# Input.net
KiCad netlist of a schematic drawn in Altium Designer
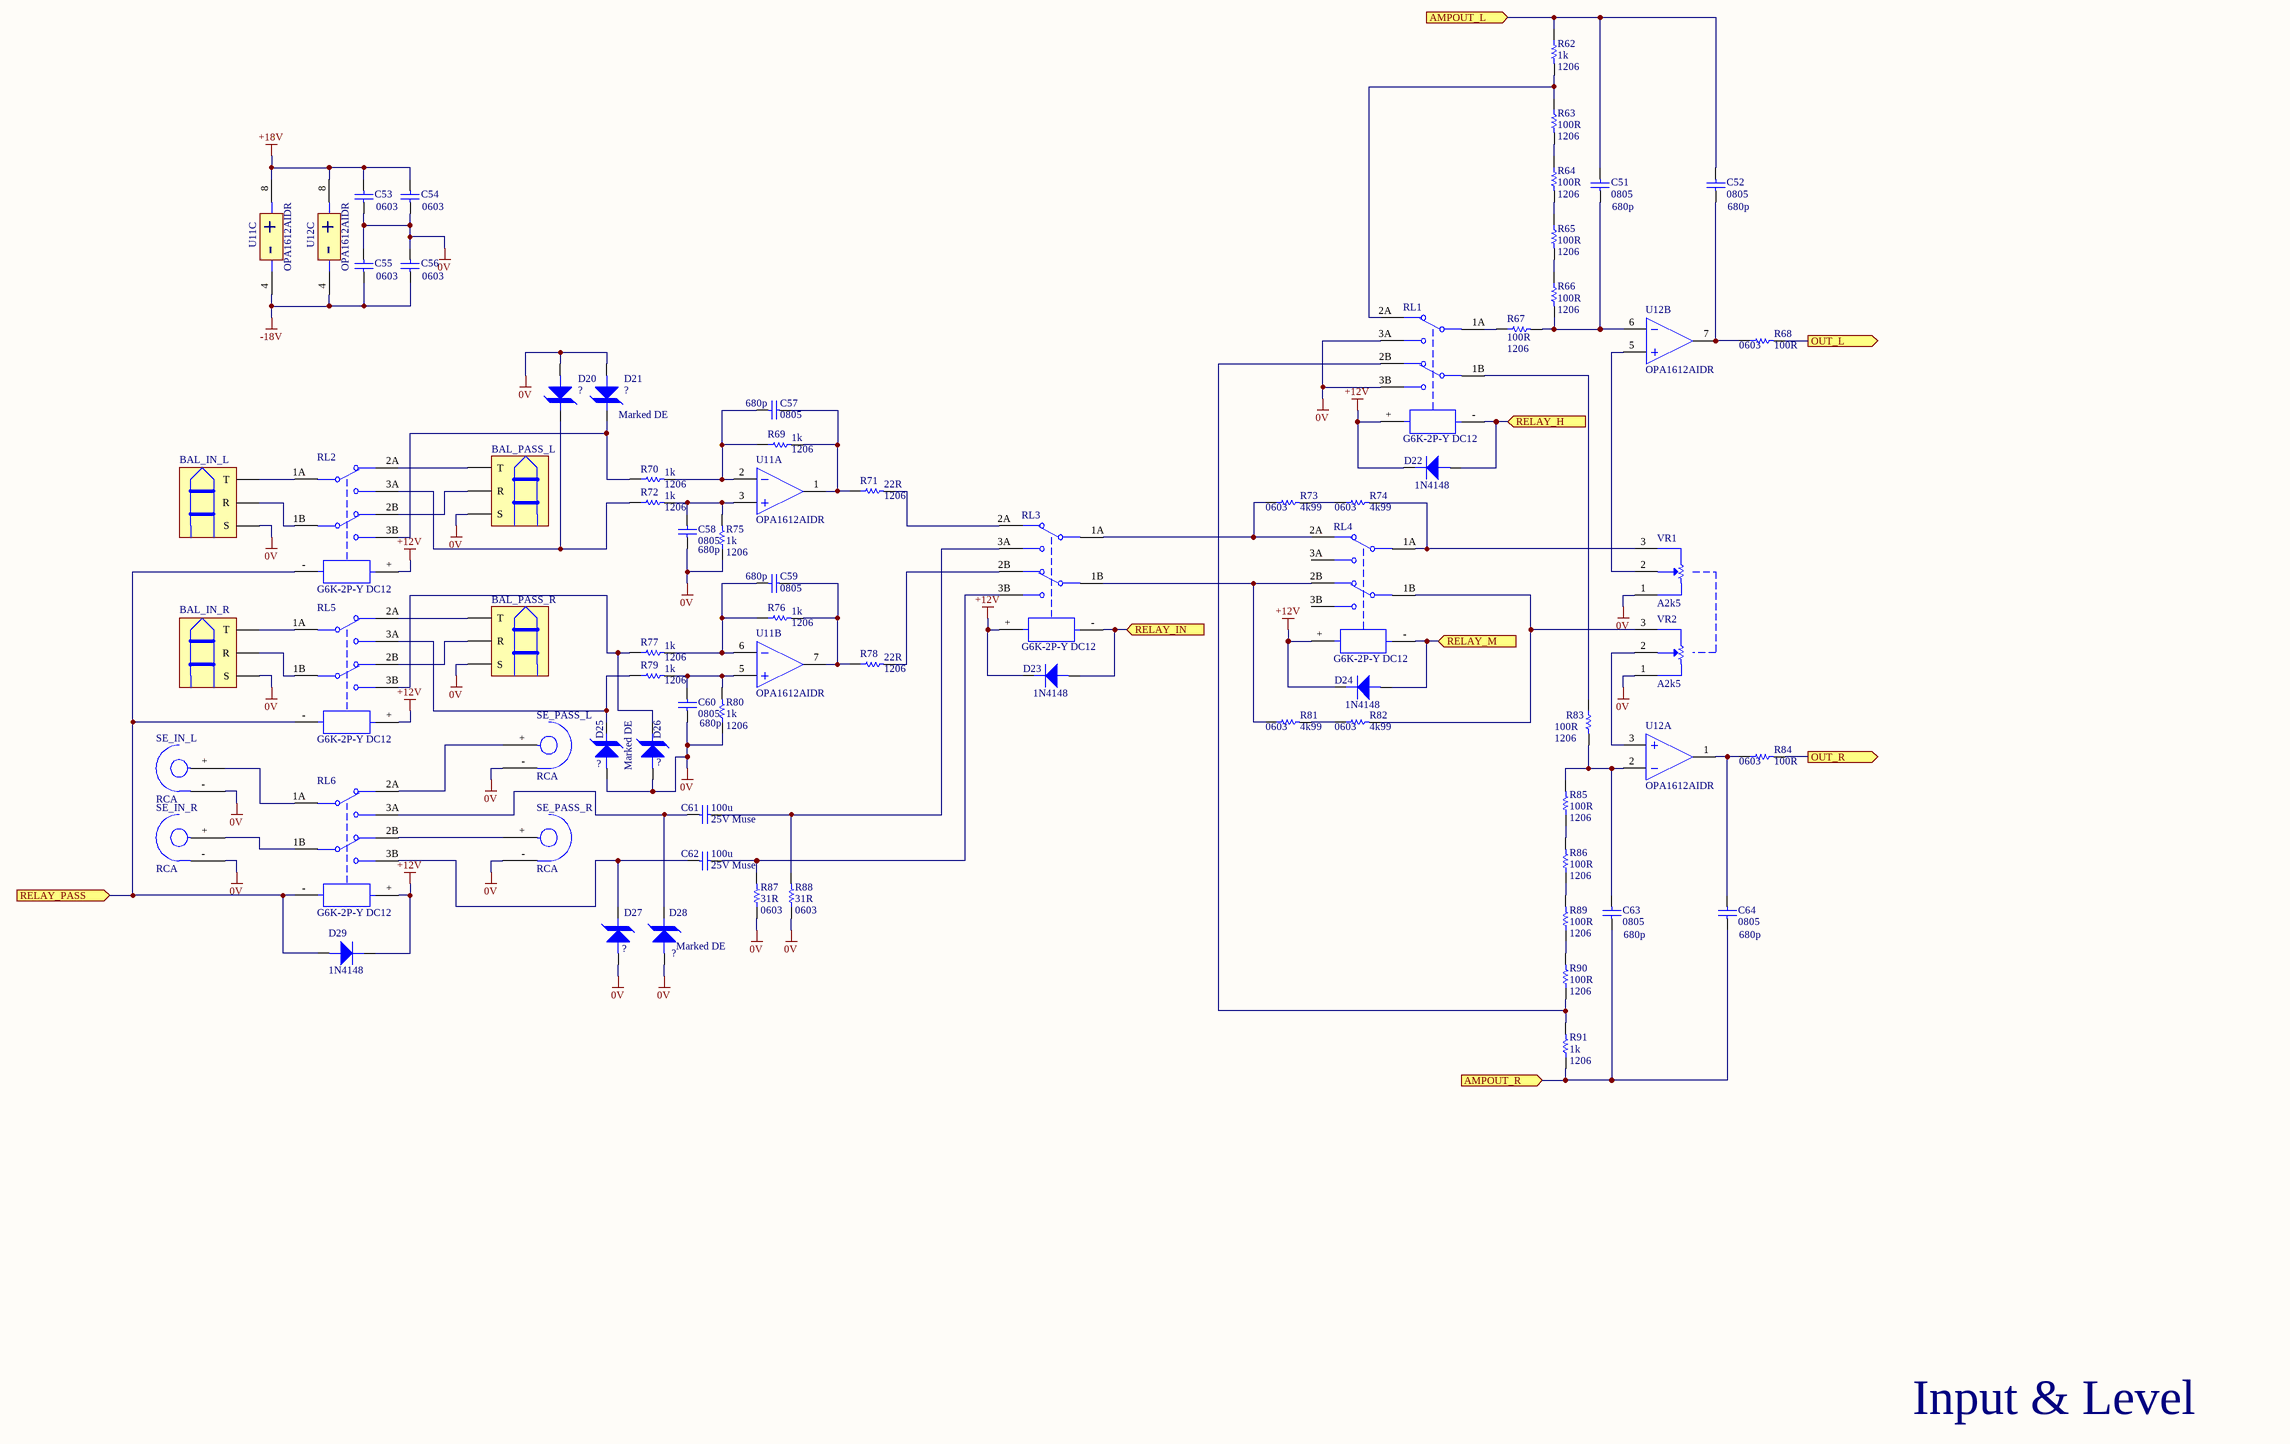
[diagram p0: Input.SchDoc]

(export (version "E")
  (design (tool "Eeschema 10.0.6"))
  (components
    (comp (ref "BAL_IN_L")
      (value "SJ-63053A")
      (footprint "SJ-63053A")
      (fields (field (name "MANUFACTURER") "Same Sky"))
      (libsource (lib "Topping_L50") (part "SJ-63053A"))
    )
    (comp (ref "BAL_IN_R")
      (value "SJ-63053A")
      (footprint "SJ-63053A")
      (fields (field (name "MANUFACTURER") "Same Sky"))
      (libsource (lib "Topping_L50") (part "SJ-63053A"))
    )
    (comp (ref "BAL_PASS_L")
      (value "SJ-63053A")
      (footprint "SJ-63053A")
      (fields (field (name "MANUFACTURER") "Same Sky"))
      (libsource (lib "") (part "SJ-63053A_1"))
    )
    (comp (ref "BAL_PASS_R")
      (value "SJ-63053A")
      (footprint "SJ-63053A")
      (fields (field (name "MANUFACTURER") "Same Sky"))
      (libsource (lib "") (part "SJ-63053A_1"))
    )
    (comp (ref "C51")
      (value "680p")
      (footprint "CAPC2012X14N")
      (description "Generic MLCC 0805 Non Polarized Capacitor")
      (fields
        (field (name "MANUFACTURER") "Generic")
        (field (name "PACKAGE") "0805")
        (field (name "Comment") "C_MLCC_0805")
      )
      (libsource (lib "Topping_L50") (part "C_MLCC_0805"))
    )
    (comp (ref "C52")
      (value "680p")
      (footprint "CAPC2012X14N")
      (description "Generic MLCC 0805 Non Polarized Capacitor")
      (fields
        (field (name "MANUFACTURER") "Generic")
        (field (name "PACKAGE") "0805")
        (field (name "Comment") "C_MLCC_0805")
      )
      (libsource (lib "Topping_L50") (part "C_MLCC_0805"))
    )
    (comp (ref "C53")
      (value "C_MLCC_0603")
      (footprint "CAPC1608X09N")
      (description "Generic MLCC 0603 Non Polarized Capacitor")
      (fields (field (name "MANUFACTURER") "Generic") (field (name "PACKAGE") "0603"))
      (libsource (lib "Topping_L50") (part "C_MLCC_0603"))
    )
    (comp (ref "C54")
      (value "C_MLCC_0603")
      (footprint "CAPC1608X09N")
      (description "Generic MLCC 0603 Non Polarized Capacitor")
      (fields (field (name "MANUFACTURER") "Generic") (field (name "PACKAGE") "0603"))
      (libsource (lib "Topping_L50") (part "C_MLCC_0603"))
    )
    (comp (ref "C55")
      (value "C_MLCC_0603")
      (footprint "CAPC1608X09N")
      (description "Generic MLCC 0603 Non Polarized Capacitor")
      (fields (field (name "MANUFACTURER") "Generic") (field (name "PACKAGE") "0603"))
      (libsource (lib "Topping_L50") (part "C_MLCC_0603"))
    )
    (comp (ref "C56")
      (value "C_MLCC_0603")
      (footprint "CAPC1608X09N")
      (description "Generic MLCC 0603 Non Polarized Capacitor")
      (fields (field (name "MANUFACTURER") "Generic") (field (name "PACKAGE") "0603"))
      (libsource (lib "Topping_L50") (part "C_MLCC_0603"))
    )
    (comp (ref "C57")
      (value "680p")
      (footprint "CAPC2012X14N")
      (description "Generic MLCC 0805 Non Polarized Capacitor")
      (fields
        (field (name "MANUFACTURER") "Generic")
        (field (name "PACKAGE") "0805")
        (field (name "Comment") "C_MLCC_0805")
      )
      (libsource (lib "Topping_L50") (part "C_MLCC_0805"))
    )
    (comp (ref "C58")
      (value "680p")
      (footprint "CAPC2012X14N")
      (description "Generic MLCC 0805 Non Polarized Capacitor")
      (fields
        (field (name "MANUFACTURER") "Generic")
        (field (name "PACKAGE") "0805")
        (field (name "Comment") "C_MLCC_0805")
      )
      (libsource (lib "Topping_L50") (part "C_MLCC_0805"))
    )
    (comp (ref "C59")
      (value "680p")
      (footprint "CAPC2012X14N")
      (description "Generic MLCC 0805 Non Polarized Capacitor")
      (fields
        (field (name "MANUFACTURER") "Generic")
        (field (name "PACKAGE") "0805")
        (field (name "Comment") "C_MLCC_0805")
      )
      (libsource (lib "Topping_L50") (part "C_MLCC_0805"))
    )
    (comp (ref "C60")
      (value "680p")
      (footprint "CAPC2012X14N")
      (description "Generic MLCC 0805 Non Polarized Capacitor")
      (fields
        (field (name "MANUFACTURER") "Generic")
        (field (name "PACKAGE") "0805")
        (field (name "Comment") "C_MLCC_0805")
      )
      (libsource (lib "Topping_L50") (part "C_MLCC_0805"))
    )
    (comp (ref "C61")
      (value "100u")
      (footprint "CAPC2012X14N")
      (description "Generic MLCC 0805 Non Polarized Capacitor")
      (fields
        (field (name "MANUFACTURER") "Generic")
        (field (name "NOTES") "25V Muse")
        (field (name "Comment") "C_MLCC_0805")
      )
      (libsource (lib "Topping_L50") (part "C_MLCC_0805"))
    )
    (comp (ref "C62")
      (value "100u")
      (footprint "CAPC2012X14N")
      (description "Generic MLCC 0805 Non Polarized Capacitor")
      (fields
        (field (name "MANUFACTURER") "Generic")
        (field (name "NOTES") "25V Muse")
        (field (name "Comment") "C_MLCC_0805")
      )
      (libsource (lib "Topping_L50") (part "C_MLCC_0805"))
    )
    (comp (ref "C63")
      (value "680p")
      (footprint "CAPC2012X14N")
      (description "Generic MLCC 0805 Non Polarized Capacitor")
      (fields
        (field (name "MANUFACTURER") "Generic")
        (field (name "PACKAGE") "0805")
        (field (name "Comment") "C_MLCC_0805")
      )
      (libsource (lib "Topping_L50") (part "C_MLCC_0805"))
    )
    (comp (ref "C64")
      (value "680p")
      (footprint "CAPC2012X14N")
      (description "Generic MLCC 0805 Non Polarized Capacitor")
      (fields
        (field (name "MANUFACTURER") "Generic")
        (field (name "PACKAGE") "0805")
        (field (name "Comment") "C_MLCC_0805")
      )
      (libsource (lib "Topping_L50") (part "C_MLCC_0805"))
    )
    (comp (ref "D20")
      (value "?")
      (footprint "DIOM4336X24N")
      (description "Generic TVS diode")
      (fields (field (name "MANUFACTURER") "Bourns") (field (name "MANUFACTURER PART NUMBER") "SMBJ30A"))
      (libsource (lib "Topping_L50") (part "TVS"))
    )
    (comp (ref "D21")
      (value "?")
      (footprint "DIOM4336X24N")
      (description "Generic TVS diode")
      (fields (field (name "MANUFACTURER") "Bourns") (field (name "MANUFACTURER PART NUMBER") "SMBJ30A"))
      (libsource (lib "Topping_L50") (part "TVS"))
    )
    (comp (ref "D22")
      (value "1N4148")
      (description "Generic small signal diode")
      (fields (field (name "MANUFACTURER") "Generic") (field (name "MANUFACTURER PART NUMBER") "BAT48ZFILM"))
      (libsource (lib "Topping_L50") (part "1N4148"))
    )
    (comp (ref "D23")
      (value "1N4148")
      (description "Generic small signal diode")
      (fields (field (name "MANUFACTURER") "Generic") (field (name "MANUFACTURER PART NUMBER") "BAT48ZFILM"))
      (libsource (lib "Topping_L50") (part "1N4148"))
    )
    (comp (ref "D24")
      (value "1N4148")
      (description "Generic small signal diode")
      (fields (field (name "MANUFACTURER") "Generic") (field (name "MANUFACTURER PART NUMBER") "BAT48ZFILM"))
      (libsource (lib "Topping_L50") (part "1N4148"))
    )
    (comp (ref "D25")
      (value "?")
      (footprint "DIOM4336X24N")
      (description "Generic TVS diode")
      (fields (field (name "MANUFACTURER") "Bourns") (field (name "MANUFACTURER PART NUMBER") "SMBJ30A"))
      (libsource (lib "Topping_L50") (part "TVS"))
    )
    (comp (ref "D26")
      (value "?")
      (footprint "DIOM4336X24N")
      (description "Generic TVS diode")
      (fields (field (name "MANUFACTURER") "Bourns") (field (name "MANUFACTURER PART NUMBER") "SMBJ30A"))
      (libsource (lib "Topping_L50") (part "TVS"))
    )
    (comp (ref "D27")
      (value "?")
      (footprint "DIOM4336X24N")
      (description "Generic TVS diode")
      (fields (field (name "MANUFACTURER") "Bourns") (field (name "MANUFACTURER PART NUMBER") "SMBJ30A"))
      (libsource (lib "Topping_L50") (part "TVS"))
    )
    (comp (ref "D28")
      (value "?")
      (footprint "DIOM4336X24N")
      (description "Generic TVS diode")
      (fields (field (name "MANUFACTURER") "Bourns") (field (name "MANUFACTURER PART NUMBER") "SMBJ30A"))
      (libsource (lib "Topping_L50") (part "TVS"))
    )
    (comp (ref "D29")
      (value "1N4148")
      (description "Generic small signal diode")
      (fields (field (name "MANUFACTURER") "Generic") (field (name "MANUFACTURER PART NUMBER") "BAT48ZFILM"))
      (libsource (lib "Topping_L50") (part "1N4148"))
    )
    (comp (ref "R62")
      (value "1k")
      (footprint "RESC3116X06N")
      (description "Generic 1206 Single Resistor")
      (fields
        (field (name "MANUFACTURER") "Generic")
        (field (name "PACKAGE") "1206")
        (field (name "Comment") "R")
      )
      (libsource (lib "Topping_L50") (part "R_1206"))
    )
    (comp (ref "R63")
      (value "100R")
      (footprint "RESC3116X06N")
      (description "Generic 1206 Single Resistor")
      (fields
        (field (name "MANUFACTURER") "Generic")
        (field (name "PACKAGE") "1206")
        (field (name "Comment") "R")
      )
      (libsource (lib "Topping_L50") (part "R_1206"))
    )
    (comp (ref "R64")
      (value "100R")
      (footprint "RESC3116X06N")
      (description "Generic 1206 Single Resistor")
      (fields
        (field (name "MANUFACTURER") "Generic")
        (field (name "PACKAGE") "1206")
        (field (name "Comment") "R")
      )
      (libsource (lib "Topping_L50") (part "R_1206"))
    )
    (comp (ref "R65")
      (value "100R")
      (footprint "RESC3116X06N")
      (description "Generic 1206 Single Resistor")
      (fields
        (field (name "MANUFACTURER") "Generic")
        (field (name "PACKAGE") "1206")
        (field (name "Comment") "R")
      )
      (libsource (lib "Topping_L50") (part "R_1206"))
    )
    (comp (ref "R66")
      (value "100R")
      (footprint "RESC3116X06N")
      (description "Generic 1206 Single Resistor")
      (fields
        (field (name "MANUFACTURER") "Generic")
        (field (name "PACKAGE") "1206")
        (field (name "Comment") "R")
      )
      (libsource (lib "Topping_L50") (part "R_1206"))
    )
    (comp (ref "R67")
      (value "100R")
      (footprint "RESC3116X06N")
      (description "Generic 1206 Single Resistor")
      (fields
        (field (name "MANUFACTURER") "Generic")
        (field (name "PACKAGE") "1206")
        (field (name "Comment") "R")
      )
      (libsource (lib "Topping_L50") (part "R_1206"))
    )
    (comp (ref "R68")
      (value "100R")
      (footprint "RESC1608X06N")
      (description "Generic 0603 Single Resistor")
      (fields
        (field (name "MANUFACTURER") "Generic")
        (field (name "PACKAGE") "0603")
        (field (name "Comment") "R")
      )
      (libsource (lib "Topping_L50") (part "R_0603"))
    )
    (comp (ref "R69")
      (value "1k")
      (footprint "RESC3116X06N")
      (description "Generic 1206 Single Resistor")
      (fields
        (field (name "MANUFACTURER") "Generic")
        (field (name "PACKAGE") "1206")
        (field (name "Comment") "R")
      )
      (libsource (lib "Topping_L50") (part "R_1206"))
    )
    (comp (ref "R70")
      (value "1k")
      (footprint "RESC3116X06N")
      (description "Generic 1206 Single Resistor")
      (fields
        (field (name "MANUFACTURER") "Generic")
        (field (name "PACKAGE") "1206")
        (field (name "Comment") "R")
      )
      (libsource (lib "Topping_L50") (part "R_1206"))
    )
    (comp (ref "R71")
      (value "22R")
      (footprint "RESC3116X06N")
      (description "Generic 1206 Single Resistor")
      (fields
        (field (name "MANUFACTURER") "Generic")
        (field (name "PACKAGE") "1206")
        (field (name "Comment") "R")
      )
      (libsource (lib "Topping_L50") (part "R_1206"))
    )
    (comp (ref "R72")
      (value "1k")
      (footprint "RESC3116X06N")
      (description "Generic 1206 Single Resistor")
      (fields
        (field (name "MANUFACTURER") "Generic")
        (field (name "PACKAGE") "1206")
        (field (name "Comment") "R")
      )
      (libsource (lib "Topping_L50") (part "R_1206"))
    )
    (comp (ref "R73")
      (value "4k99")
      (footprint "RESC1608X06N")
      (description "Generic 0603 Single Resistor")
      (fields
        (field (name "MANUFACTURER") "Generic")
        (field (name "PACKAGE") "0603")
        (field (name "Comment") "R")
      )
      (libsource (lib "Topping_L50") (part "R_0603"))
    )
    (comp (ref "R74")
      (value "4k99")
      (footprint "RESC1608X06N")
      (description "Generic 0603 Single Resistor")
      (fields
        (field (name "MANUFACTURER") "Generic")
        (field (name "PACKAGE") "0603")
        (field (name "Comment") "R")
      )
      (libsource (lib "Topping_L50") (part "R_0603"))
    )
    (comp (ref "R75")
      (value "1k")
      (footprint "RESC3116X06N")
      (description "Generic 1206 Single Resistor")
      (fields
        (field (name "MANUFACTURER") "Generic")
        (field (name "PACKAGE") "1206")
        (field (name "Comment") "R")
      )
      (libsource (lib "Topping_L50") (part "R_1206"))
    )
    (comp (ref "R76")
      (value "1k")
      (footprint "RESC3116X06N")
      (description "Generic 1206 Single Resistor")
      (fields
        (field (name "MANUFACTURER") "Generic")
        (field (name "PACKAGE") "1206")
        (field (name "Comment") "R")
      )
      (libsource (lib "Topping_L50") (part "R_1206"))
    )
    (comp (ref "R77")
      (value "1k")
      (footprint "RESC3116X06N")
      (description "Generic 1206 Single Resistor")
      (fields
        (field (name "MANUFACTURER") "Generic")
        (field (name "PACKAGE") "1206")
        (field (name "Comment") "R")
      )
      (libsource (lib "Topping_L50") (part "R_1206"))
    )
    (comp (ref "R78")
      (value "22R")
      (footprint "RESC3116X06N")
      (description "Generic 1206 Single Resistor")
      (fields
        (field (name "MANUFACTURER") "Generic")
        (field (name "PACKAGE") "1206")
        (field (name "Comment") "R")
      )
      (libsource (lib "Topping_L50") (part "R_1206"))
    )
    (comp (ref "R79")
      (value "1k")
      (footprint "RESC3116X06N")
      (description "Generic 1206 Single Resistor")
      (fields
        (field (name "MANUFACTURER") "Generic")
        (field (name "PACKAGE") "1206")
        (field (name "Comment") "R")
      )
      (libsource (lib "Topping_L50") (part "R_1206"))
    )
    (comp (ref "R80")
      (value "1k")
      (footprint "RESC3116X06N")
      (description "Generic 1206 Single Resistor")
      (fields
        (field (name "MANUFACTURER") "Generic")
        (field (name "PACKAGE") "1206")
        (field (name "Comment") "R")
      )
      (libsource (lib "Topping_L50") (part "R_1206"))
    )
    (comp (ref "R81")
      (value "4k99")
      (footprint "RESC1608X06N")
      (description "Generic 0603 Single Resistor")
      (fields
        (field (name "MANUFACTURER") "Generic")
        (field (name "PACKAGE") "0603")
        (field (name "Comment") "R")
      )
      (libsource (lib "Topping_L50") (part "R_0603"))
    )
    (comp (ref "R82")
      (value "4k99")
      (footprint "RESC1608X06N")
      (description "Generic 0603 Single Resistor")
      (fields
        (field (name "MANUFACTURER") "Generic")
        (field (name "PACKAGE") "0603")
        (field (name "Comment") "R")
      )
      (libsource (lib "Topping_L50") (part "R_0603"))
    )
    (comp (ref "R83")
      (value "100R")
      (footprint "RESC3116X06N")
      (description "Generic 1206 Single Resistor")
      (fields
        (field (name "MANUFACTURER") "Generic")
        (field (name "PACKAGE") "1206")
        (field (name "Comment") "R")
      )
      (libsource (lib "Topping_L50") (part "R_1206"))
    )
    (comp (ref "R84")
      (value "100R")
      (footprint "RESC1608X06N")
      (description "Generic 0603 Single Resistor")
      (fields
        (field (name "MANUFACTURER") "Generic")
        (field (name "PACKAGE") "0603")
        (field (name "Comment") "R")
      )
      (libsource (lib "Topping_L50") (part "R_0603"))
    )
    (comp (ref "R85")
      (value "100R")
      (footprint "RESC3116X06N")
      (description "Generic 1206 Single Resistor")
      (fields
        (field (name "MANUFACTURER") "Generic")
        (field (name "PACKAGE") "1206")
        (field (name "Comment") "R")
      )
      (libsource (lib "Topping_L50") (part "R_1206"))
    )
    (comp (ref "R86")
      (value "100R")
      (footprint "RESC3116X06N")
      (description "Generic 1206 Single Resistor")
      (fields
        (field (name "MANUFACTURER") "Generic")
        (field (name "PACKAGE") "1206")
        (field (name "Comment") "R")
      )
      (libsource (lib "Topping_L50") (part "R_1206"))
    )
    (comp (ref "R87")
      (value "31R")
      (footprint "RESC1608X06N")
      (description "Generic 0603 Single Resistor")
      (fields
        (field (name "MANUFACTURER") "Generic")
        (field (name "PACKAGE") "0603")
        (field (name "Comment") "R")
      )
      (libsource (lib "Topping_L50") (part "R_0603"))
    )
    (comp (ref "R88")
      (value "31R")
      (footprint "RESC1608X06N")
      (description "Generic 0603 Single Resistor")
      (fields
        (field (name "MANUFACTURER") "Generic")
        (field (name "PACKAGE") "0603")
        (field (name "Comment") "R")
      )
      (libsource (lib "Topping_L50") (part "R_0603"))
    )
    (comp (ref "R89")
      (value "100R")
      (footprint "RESC3116X06N")
      (description "Generic 1206 Single Resistor")
      (fields
        (field (name "MANUFACTURER") "Generic")
        (field (name "PACKAGE") "1206")
        (field (name "Comment") "R")
      )
      (libsource (lib "Topping_L50") (part "R_1206"))
    )
    (comp (ref "R90")
      (value "100R")
      (footprint "RESC3116X06N")
      (description "Generic 1206 Single Resistor")
      (fields
        (field (name "MANUFACTURER") "Generic")
        (field (name "PACKAGE") "1206")
        (field (name "Comment") "R")
      )
      (libsource (lib "Topping_L50") (part "R_1206"))
    )
    (comp (ref "R91")
      (value "1k")
      (footprint "RESC3116X06N")
      (description "Generic 1206 Single Resistor")
      (fields
        (field (name "MANUFACTURER") "Generic")
        (field (name "PACKAGE") "1206")
        (field (name "Comment") "R")
      )
      (libsource (lib "Topping_L50") (part "R_1206"))
    )
    (comp (ref "RL1")
      (value "G6K-2P-Y DC12")
      (footprint "G6K-2P-Y")
      (description "Low Signal Relays - PCB Gullwing NoLatch 3.2 DPDT 12VDC 100mW T/R")
      (fields (field (name "MANUFACTURER") "Omron"))
      (libsource (lib "Topping_L50") (part "G6K-2P-Y DC12"))
    )
    (comp (ref "RL2")
      (value "G6K-2P-Y DC12")
      (footprint "G6K-2P-Y")
      (description "Low Signal Relays - PCB Gullwing NoLatch 3.2 DPDT 12VDC 100mW T/R")
      (fields (field (name "MANUFACTURER") "Omron"))
      (libsource (lib "Topping_L50") (part "G6K-2P-Y DC12"))
    )
    (comp (ref "RL3")
      (value "G6K-2P-Y DC12")
      (footprint "G6K-2P-Y")
      (description "Low Signal Relays - PCB Gullwing NoLatch 3.2 DPDT 12VDC 100mW T/R")
      (fields (field (name "MANUFACTURER") "Omron"))
      (libsource (lib "Topping_L50") (part "G6K-2P-Y DC12"))
    )
    (comp (ref "RL4")
      (value "G6K-2P-Y DC12")
      (footprint "G6K-2P-Y")
      (description "Low Signal Relays - PCB Gullwing NoLatch 3.2 DPDT 12VDC 100mW T/R")
      (fields (field (name "MANUFACTURER") "Omron"))
      (libsource (lib "Topping_L50") (part "G6K-2P-Y DC12"))
    )
    (comp (ref "RL5")
      (value "G6K-2P-Y DC12")
      (footprint "G6K-2P-Y")
      (description "Low Signal Relays - PCB Gullwing NoLatch 3.2 DPDT 12VDC 100mW T/R")
      (fields (field (name "MANUFACTURER") "Omron"))
      (libsource (lib "Topping_L50") (part "G6K-2P-Y DC12"))
    )
    (comp (ref "RL6")
      (value "G6K-2P-Y DC12")
      (footprint "G6K-2P-Y")
      (description "Low Signal Relays - PCB Gullwing NoLatch 3.2 DPDT 12VDC 100mW T/R")
      (fields (field (name "MANUFACTURER") "Omron"))
      (libsource (lib "Topping_L50") (part "G6K-2P-Y DC12"))
    )
    (comp (ref "SE_IN_L")
      (value "RCA")
      (description "Generic RCA Connector")
      (fields (field (name "MANUFACTURER") "Generic"))
      (libsource (lib "") (part "RCA_1"))
    )
    (comp (ref "SE_IN_R")
      (value "RCA")
      (description "Generic RCA Connector")
      (fields (field (name "MANUFACTURER") "Generic"))
      (libsource (lib "") (part "RCA_1"))
    )
    (comp (ref "SE_PASS_L")
      (value "RCA")
      (description "Generic RCA Connector")
      (fields (field (name "MANUFACTURER") "Generic"))
      (libsource (lib "Topping_L50") (part "RCA"))
    )
    (comp (ref "SE_PASS_R")
      (value "RCA")
      (description "Generic RCA Connector")
      (fields (field (name "MANUFACTURER") "Generic"))
      (libsource (lib "Topping_L50") (part "RCA"))
    )
    (comp (ref "U11")
      (value "OPA1612AIDR")
      (footprint "SOIC127P600X175-8L")
      (description "High-Performance, Bipolar-Input Audio Operational Amplifiers")
      (fields (field (name "MANUFACTURER") "Texas Instruments"))
      (libsource (lib "") (part "OPA1612AIDR_1"))
    )
    (comp (ref "U12")
      (value "OPA1612AIDR")
      (footprint "SOIC127P600X175-8L")
      (description "High-Performance, Bipolar-Input Audio Operational Amplifiers")
      (fields (field (name "MANUFACTURER") "Texas Instruments"))
      (libsource (lib "") (part "OPA1612AIDR_1"))
    )
    (comp (ref "VR1")
      (value "A2k5")
      (description "Generic Pot")
      (fields (field (name "MANUFACTURER") "Generic") (field (name "Comment") "Pot"))
      (libsource (lib "Topping_L50") (part "Pot"))
    )
    (comp (ref "VR2")
      (value "A2k5")
      (description "Generic Pot")
      (fields (field (name "MANUFACTURER") "Generic") (field (name "Comment") "Pot"))
      (libsource (lib "Topping_L50") (part "Pot"))
    )
  )
  (nets
    (net (code "1") (name "+12V") (class "Default")
      (node (ref "D22") (pin "K") (pinfunction "K_K") (pintype "passive"))
      (node (ref "D23") (pin "K") (pinfunction "K_K") (pintype "passive"))
      (node (ref "D24") (pin "K") (pinfunction "K_K") (pintype "passive"))
      (node (ref "D29") (pin "K") (pinfunction "K_K") (pintype "passive"))
      (node (ref "RL1") (pin "+") (pinfunction "+_+") (pintype "passive"))
      (node (ref "RL2") (pin "+") (pinfunction "+_+") (pintype "passive"))
      (node (ref "RL3") (pin "+") (pinfunction "+_+") (pintype "passive"))
      (node (ref "RL4") (pin "+") (pinfunction "+_+") (pintype "passive"))
      (node (ref "RL5") (pin "+") (pinfunction "+_+") (pintype "passive"))
      (node (ref "RL6") (pin "+") (pinfunction "+_+") (pintype "passive"))
    )
    (net (code "2") (name "+18V") (class "Default")
      (node (ref "C53") (pin "2") (pinfunction "2_2") (pintype "passive"))
      (node (ref "C54") (pin "2") (pinfunction "2_2") (pintype "passive"))
      (node (ref "U11") (pin "8") (pinfunction "VCC+_8") (pintype "power_in"))
      (node (ref "U12") (pin "8") (pinfunction "VCC+_8") (pintype "power_in"))
    )
    (net (code "3") (name "-18V") (class "Default")
      (node (ref "C55") (pin "1") (pinfunction "1_1") (pintype "passive"))
      (node (ref "C56") (pin "1") (pinfunction "1_1") (pintype "passive"))
      (node (ref "U11") (pin "4") (pinfunction "VCC-_4") (pintype "power_in"))
      (node (ref "U12") (pin "4") (pinfunction "VCC-_4") (pintype "power_in"))
    )
    (net (code "4") (name "/AMPOUT_L") (class "Default")
      (node (ref "C51") (pin "2") (pinfunction "2_2") (pintype "passive"))
      (node (ref "C52") (pin "2") (pinfunction "2_2") (pintype "passive"))
      (node (ref "R62") (pin "1") (pinfunction "1_1") (pintype "passive"))
    )
    (net (code "5") (name "/AMPOUT_R") (class "Default")
      (node (ref "C63") (pin "1") (pinfunction "1_1") (pintype "passive"))
      (node (ref "C64") (pin "1") (pinfunction "1_1") (pintype "passive"))
      (node (ref "R91") (pin "1") (pinfunction "1_1") (pintype "passive"))
    )
    (net (code "6") (name "/OUT_L") (class "Default")
      (node (ref "R68") (pin "2") (pinfunction "2_2") (pintype "passive"))
    )
    (net (code "7") (name "/OUT_R") (class "Default")
      (node (ref "R84") (pin "2") (pinfunction "2_2") (pintype "passive"))
    )
    (net (code "8") (name "/RELAY_H") (class "Default")
      (node (ref "D22") (pin "A") (pinfunction "A_A") (pintype "passive"))
      (node (ref "RL1") (pin "-") (pinfunction "-_-") (pintype "passive"))
    )
    (net (code "9") (name "/RELAY_IN") (class "Default")
      (node (ref "D23") (pin "A") (pinfunction "A_A") (pintype "passive"))
      (node (ref "RL3") (pin "-") (pinfunction "-_-") (pintype "passive"))
    )
    (net (code "10") (name "/RELAY_M") (class "Default")
      (node (ref "D24") (pin "A") (pinfunction "A_A") (pintype "passive"))
      (node (ref "RL4") (pin "-") (pinfunction "-_-") (pintype "passive"))
    )
    (net (code "11") (name "/RELAY_PASS") (class "Default")
      (node (ref "D29") (pin "A") (pinfunction "A_A") (pintype "passive"))
      (node (ref "RL2") (pin "-") (pinfunction "-_-") (pintype "passive"))
      (node (ref "RL5") (pin "-") (pinfunction "-_-") (pintype "passive"))
      (node (ref "RL6") (pin "-") (pinfunction "-_-") (pintype "passive"))
    )
    (net (code "12") (name "0V") (class "Default")
      (node (ref "BAL_IN_L") (pin "S") (pinfunction "S_S") (pintype "passive"))
      (node (ref "BAL_IN_R") (pin "S") (pinfunction "S_S") (pintype "passive"))
      (node (ref "BAL_PASS_L") (pin "S") (pinfunction "S_S") (pintype "passive"))
      (node (ref "BAL_PASS_R") (pin "S") (pinfunction "S_S") (pintype "passive"))
      (node (ref "C53") (pin "1") (pinfunction "1_1") (pintype "passive"))
      (node (ref "C54") (pin "1") (pinfunction "1_1") (pintype "passive"))
      (node (ref "C55") (pin "2") (pinfunction "2_2") (pintype "passive"))
      (node (ref "C56") (pin "2") (pinfunction "2_2") (pintype "passive"))
      (node (ref "C58") (pin "1") (pinfunction "1_1") (pintype "passive"))
      (node (ref "C60") (pin "1") (pinfunction "1_1") (pintype "passive"))
      (node (ref "D20") (pin "A") (pinfunction "A_A") (pintype "passive"))
      (node (ref "D21") (pin "A") (pinfunction "A_A") (pintype "passive"))
      (node (ref "D25") (pin "A") (pinfunction "A_A") (pintype "passive"))
      (node (ref "D26") (pin "A") (pinfunction "A_A") (pintype "passive"))
      (node (ref "D27") (pin "A") (pinfunction "A_A") (pintype "passive"))
      (node (ref "D28") (pin "A") (pinfunction "A_A") (pintype "passive"))
      (node (ref "R75") (pin "1") (pinfunction "1_1") (pintype "passive"))
      (node (ref "R80") (pin "1") (pinfunction "1_1") (pintype "passive"))
      (node (ref "R87") (pin "1") (pinfunction "1_1") (pintype "passive"))
      (node (ref "R88") (pin "1") (pinfunction "1_1") (pintype "passive"))
      (node (ref "RL1") (pin "3A") (pinfunction "3A_3A") (pintype "passive"))
      (node (ref "RL1") (pin "3B") (pinfunction "3B_3B") (pintype "passive"))
      (node (ref "SE_IN_L") (pin "-") (pinfunction "-_-") (pintype "passive"))
      (node (ref "SE_IN_R") (pin "-") (pinfunction "-_-") (pintype "passive"))
      (node (ref "SE_PASS_L") (pin "-") (pinfunction "-_-") (pintype "passive"))
      (node (ref "SE_PASS_R") (pin "-") (pinfunction "-_-") (pintype "passive"))
      (node (ref "VR1") (pin "1") (pinfunction "1_1") (pintype "passive"))
      (node (ref "VR2") (pin "1") (pinfunction "1_1") (pintype "passive"))
    )
    (net (code "13") (name "Net-(BAL_IN_L-PadR)") (class "Default")
      (node (ref "BAL_IN_L") (pin "R") (pinfunction "R_R") (pintype "passive"))
      (node (ref "RL2") (pin "1B") (pinfunction "1B_1B") (pintype "passive"))
    )
    (net (code "14") (name "Net-(BAL_IN_L-PadT)") (class "Default")
      (node (ref "BAL_IN_L") (pin "T") (pinfunction "T_T") (pintype "passive"))
      (node (ref "RL2") (pin "1A") (pinfunction "1A_1A") (pintype "passive"))
    )
    (net (code "15") (name "Net-(BAL_IN_R-PadR)") (class "Default")
      (node (ref "BAL_IN_R") (pin "R") (pinfunction "R_R") (pintype "passive"))
      (node (ref "RL5") (pin "1B") (pinfunction "1B_1B") (pintype "passive"))
    )
    (net (code "16") (name "Net-(BAL_IN_R-PadT)") (class "Default")
      (node (ref "BAL_IN_R") (pin "T") (pinfunction "T_T") (pintype "passive"))
      (node (ref "RL5") (pin "1A") (pinfunction "1A_1A") (pintype "passive"))
    )
    (net (code "17") (name "Net-(BAL_PASS_L-PadR)") (class "Default")
      (node (ref "BAL_PASS_L") (pin "R") (pinfunction "R_R") (pintype "passive"))
      (node (ref "RL2") (pin "2B") (pinfunction "2B_2B") (pintype "passive"))
    )
    (net (code "18") (name "Net-(BAL_PASS_L-PadT)") (class "Default")
      (node (ref "BAL_PASS_L") (pin "T") (pinfunction "T_T") (pintype "passive"))
      (node (ref "RL2") (pin "2A") (pinfunction "2A_2A") (pintype "passive"))
    )
    (net (code "19") (name "Net-(BAL_PASS_R-PadR)") (class "Default")
      (node (ref "BAL_PASS_R") (pin "R") (pinfunction "R_R") (pintype "passive"))
      (node (ref "RL5") (pin "2B") (pinfunction "2B_2B") (pintype "passive"))
    )
    (net (code "20") (name "Net-(BAL_PASS_R-PadT)") (class "Default")
      (node (ref "BAL_PASS_R") (pin "T") (pinfunction "T_T") (pintype "passive"))
      (node (ref "RL5") (pin "2A") (pinfunction "2A_2A") (pintype "passive"))
    )
    (net (code "21") (name "Net-(C61-Pad1)") (class "Default")
      (node (ref "C61") (pin "1") (pinfunction "1_1") (pintype "passive"))
      (node (ref "D28") (pin "K") (pinfunction "K_K") (pintype "passive"))
      (node (ref "RL6") (pin "3A") (pinfunction "3A_3A") (pintype "passive"))
    )
    (net (code "22") (name "Net-(C61-Pad2)") (class "Default")
      (node (ref "C61") (pin "2") (pinfunction "2_2") (pintype "passive"))
      (node (ref "R88") (pin "2") (pinfunction "2_2") (pintype "passive"))
      (node (ref "RL3") (pin "3A") (pinfunction "3A_3A") (pintype "passive"))
    )
    (net (code "23") (name "Net-(C62-Pad1)") (class "Default")
      (node (ref "C62") (pin "1") (pinfunction "1_1") (pintype "passive"))
      (node (ref "D27") (pin "K") (pinfunction "K_K") (pintype "passive"))
      (node (ref "RL6") (pin "3B") (pinfunction "3B_3B") (pintype "passive"))
    )
    (net (code "24") (name "Net-(C62-Pad2)") (class "Default")
      (node (ref "C62") (pin "2") (pinfunction "2_2") (pintype "passive"))
      (node (ref "R87") (pin "2") (pinfunction "2_2") (pintype "passive"))
      (node (ref "RL3") (pin "3B") (pinfunction "3B_3B") (pintype "passive"))
    )
    (net (code "25") (name "Net-(D20-PadK)") (class "Default")
      (node (ref "D20") (pin "K") (pinfunction "K_K") (pintype "passive"))
      (node (ref "R72") (pin "1") (pinfunction "1_1") (pintype "passive"))
      (node (ref "RL2") (pin "3A") (pinfunction "3A_3A") (pintype "passive"))
    )
    (net (code "26") (name "Net-(D21-PadK)") (class "Default")
      (node (ref "D21") (pin "K") (pinfunction "K_K") (pintype "passive"))
      (node (ref "R70") (pin "1") (pinfunction "1_1") (pintype "passive"))
      (node (ref "RL2") (pin "3B") (pinfunction "3B_3B") (pintype "passive"))
    )
    (net (code "27") (name "Net-(D25-PadK)") (class "Default")
      (node (ref "D25") (pin "K") (pinfunction "K_K") (pintype "passive"))
      (node (ref "R79") (pin "1") (pinfunction "1_1") (pintype "passive"))
      (node (ref "RL5") (pin "3A") (pinfunction "3A_3A") (pintype "passive"))
    )
    (net (code "28") (name "Net-(D26-PadK)") (class "Default")
      (node (ref "D26") (pin "K") (pinfunction "K_K") (pintype "passive"))
      (node (ref "R77") (pin "1") (pinfunction "1_1") (pintype "passive"))
      (node (ref "RL5") (pin "3B") (pinfunction "3B_3B") (pintype "passive"))
    )
    (net (code "29") (name "Net-(R62-Pad2)") (class "Default")
      (node (ref "R62") (pin "2") (pinfunction "2_2") (pintype "passive"))
      (node (ref "R63") (pin "1") (pinfunction "1_1") (pintype "passive"))
      (node (ref "RL1") (pin "2A") (pinfunction "2A_2A") (pintype "passive"))
    )
    (net (code "30") (name "Net-(R63-Pad2)") (class "Default")
      (node (ref "R63") (pin "2") (pinfunction "2_2") (pintype "passive"))
      (node (ref "R64") (pin "1") (pinfunction "1_1") (pintype "passive"))
    )
    (net (code "31") (name "Net-(R64-Pad2)") (class "Default")
      (node (ref "R64") (pin "2") (pinfunction "2_2") (pintype "passive"))
      (node (ref "R65") (pin "1") (pinfunction "1_1") (pintype "passive"))
    )
    (net (code "32") (name "Net-(R65-Pad2)") (class "Default")
      (node (ref "R65") (pin "2") (pinfunction "2_2") (pintype "passive"))
      (node (ref "R66") (pin "1") (pinfunction "1_1") (pintype "passive"))
    )
    (net (code "33") (name "Net-(R67-Pad1)") (class "Default")
      (node (ref "R67") (pin "1") (pinfunction "1_1") (pintype "passive"))
      (node (ref "RL1") (pin "1A") (pinfunction "1A_1A") (pintype "passive"))
    )
    (net (code "34") (name "Net-(R71-Pad2)") (class "Default")
      (node (ref "R71") (pin "2") (pinfunction "2_2") (pintype "passive"))
      (node (ref "RL3") (pin "2A") (pinfunction "2A_2A") (pintype "passive"))
    )
    (net (code "35") (name "Net-(R73-Pad1)") (class "Default")
      (node (ref "R73") (pin "1") (pinfunction "1_1") (pintype "passive"))
      (node (ref "RL3") (pin "1A") (pinfunction "1A_1A") (pintype "passive"))
      (node (ref "RL4") (pin "2A") (pinfunction "2A_2A") (pintype "passive"))
    )
    (net (code "36") (name "Net-(R73-Pad2)") (class "Default")
      (node (ref "R73") (pin "2") (pinfunction "2_2") (pintype "passive"))
      (node (ref "R74") (pin "1") (pinfunction "1_1") (pintype "passive"))
    )
    (net (code "37") (name "Net-(R74-Pad2)") (class "Default")
      (node (ref "R74") (pin "2") (pinfunction "2_2") (pintype "passive"))
      (node (ref "RL4") (pin "1A") (pinfunction "1A_1A") (pintype "passive"))
      (node (ref "VR1") (pin "3") (pinfunction "3_3") (pintype "passive"))
    )
    (net (code "38") (name "Net-(R78-Pad2)") (class "Default")
      (node (ref "R78") (pin "2") (pinfunction "2_2") (pintype "passive"))
      (node (ref "RL3") (pin "2B") (pinfunction "2B_2B") (pintype "passive"))
    )
    (net (code "39") (name "Net-(R81-Pad1)") (class "Default")
      (node (ref "R81") (pin "1") (pinfunction "1_1") (pintype "passive"))
      (node (ref "RL3") (pin "1B") (pinfunction "1B_1B") (pintype "passive"))
      (node (ref "RL4") (pin "2B") (pinfunction "2B_2B") (pintype "passive"))
    )
    (net (code "40") (name "Net-(R81-Pad2)") (class "Default")
      (node (ref "R81") (pin "2") (pinfunction "2_2") (pintype "passive"))
      (node (ref "R82") (pin "1") (pinfunction "1_1") (pintype "passive"))
    )
    (net (code "41") (name "Net-(R82-Pad2)") (class "Default")
      (node (ref "R82") (pin "2") (pinfunction "2_2") (pintype "passive"))
      (node (ref "RL4") (pin "1B") (pinfunction "1B_1B") (pintype "passive"))
      (node (ref "VR2") (pin "3") (pinfunction "3_3") (pintype "passive"))
    )
    (net (code "42") (name "Net-(R83-Pad1)") (class "Default")
      (node (ref "R83") (pin "1") (pinfunction "1_1") (pintype "passive"))
      (node (ref "RL1") (pin "1B") (pinfunction "1B_1B") (pintype "passive"))
    )
    (net (code "43") (name "Net-(R85-Pad1)") (class "Default")
      (node (ref "R85") (pin "1") (pinfunction "1_1") (pintype "passive"))
      (node (ref "R86") (pin "2") (pinfunction "2_2") (pintype "passive"))
    )
    (net (code "44") (name "Net-(R86-Pad1)") (class "Default")
      (node (ref "R86") (pin "1") (pinfunction "1_1") (pintype "passive"))
      (node (ref "R89") (pin "2") (pinfunction "2_2") (pintype "passive"))
    )
    (net (code "45") (name "Net-(R89-Pad1)") (class "Default")
      (node (ref "R89") (pin "1") (pinfunction "1_1") (pintype "passive"))
      (node (ref "R90") (pin "2") (pinfunction "2_2") (pintype "passive"))
    )
    (net (code "46") (name "Net-(R90-Pad1)") (class "Default")
      (node (ref "R90") (pin "1") (pinfunction "1_1") (pintype "passive"))
      (node (ref "R91") (pin "2") (pinfunction "2_2") (pintype "passive"))
      (node (ref "RL1") (pin "2B") (pinfunction "2B_2B") (pintype "passive"))
    )
    (net (code "47") (name "Net-(RL6-Pad1A)") (class "Default")
      (node (ref "RL6") (pin "1A") (pinfunction "1A_1A") (pintype "passive"))
      (node (ref "SE_IN_L") (pin "+") (pinfunction "+_+") (pintype "passive"))
    )
    (net (code "48") (name "Net-(RL6-Pad1B)") (class "Default")
      (node (ref "RL6") (pin "1B") (pinfunction "1B_1B") (pintype "passive"))
      (node (ref "SE_IN_R") (pin "+") (pinfunction "+_+") (pintype "passive"))
    )
    (net (code "49") (name "Net-(RL6-Pad2A)") (class "Default")
      (node (ref "RL6") (pin "2A") (pinfunction "2A_2A") (pintype "passive"))
      (node (ref "SE_PASS_L") (pin "+") (pinfunction "+_+") (pintype "passive"))
    )
    (net (code "50") (name "Net-(RL6-Pad2B)") (class "Default")
      (node (ref "RL6") (pin "2B") (pinfunction "2B_2B") (pintype "passive"))
      (node (ref "SE_PASS_R") (pin "+") (pinfunction "+_+") (pintype "passive"))
    )
    (net (code "51") (name "Net-(U11A-IN1+)") (class "Default")
      (node (ref "C58") (pin "2") (pinfunction "2_2") (pintype "passive"))
      (node (ref "R72") (pin "2") (pinfunction "2_2") (pintype "passive"))
      (node (ref "R75") (pin "2") (pinfunction "2_2") (pintype "passive"))
      (node (ref "U11") (pin "3") (pinfunction "IN1+_3") (pintype "passive"))
    )
    (net (code "52") (name "Net-(U11A-IN1-)") (class "Default")
      (node (ref "C57") (pin "1") (pinfunction "1_1") (pintype "passive"))
      (node (ref "R69") (pin "1") (pinfunction "1_1") (pintype "passive"))
      (node (ref "R70") (pin "2") (pinfunction "2_2") (pintype "passive"))
      (node (ref "U11") (pin "2") (pinfunction "IN1-_2") (pintype "passive"))
    )
    (net (code "53") (name "Net-(U11A-OUT1)") (class "Default")
      (node (ref "C57") (pin "2") (pinfunction "2_2") (pintype "passive"))
      (node (ref "R69") (pin "2") (pinfunction "2_2") (pintype "passive"))
      (node (ref "R71") (pin "1") (pinfunction "1_1") (pintype "passive"))
      (node (ref "U11") (pin "1") (pinfunction "OUT1_1") (pintype "passive"))
    )
    (net (code "54") (name "Net-(U11B-IN2+)") (class "Default")
      (node (ref "C60") (pin "2") (pinfunction "2_2") (pintype "passive"))
      (node (ref "R79") (pin "2") (pinfunction "2_2") (pintype "passive"))
      (node (ref "R80") (pin "2") (pinfunction "2_2") (pintype "passive"))
      (node (ref "U11") (pin "5") (pinfunction "IN2+_5") (pintype "passive"))
    )
    (net (code "55") (name "Net-(U11B-IN2-)") (class "Default")
      (node (ref "C59") (pin "1") (pinfunction "1_1") (pintype "passive"))
      (node (ref "R76") (pin "1") (pinfunction "1_1") (pintype "passive"))
      (node (ref "R77") (pin "2") (pinfunction "2_2") (pintype "passive"))
      (node (ref "U11") (pin "6") (pinfunction "IN2-_6") (pintype "passive"))
    )
    (net (code "56") (name "Net-(U11B-OUT2)") (class "Default")
      (node (ref "C59") (pin "2") (pinfunction "2_2") (pintype "passive"))
      (node (ref "R76") (pin "2") (pinfunction "2_2") (pintype "passive"))
      (node (ref "R78") (pin "1") (pinfunction "1_1") (pintype "passive"))
      (node (ref "U11") (pin "7") (pinfunction "OUT2_7") (pintype "passive"))
    )
    (net (code "57") (name "Net-(U12A-IN1+)") (class "Default")
      (node (ref "U12") (pin "3") (pinfunction "IN1+_3") (pintype "passive"))
      (node (ref "VR2") (pin "2") (pinfunction "2_2") (pintype "passive"))
    )
    (net (code "58") (name "Net-(U12A-IN1-)") (class "Default")
      (node (ref "C63") (pin "2") (pinfunction "2_2") (pintype "passive"))
      (node (ref "R83") (pin "2") (pinfunction "2_2") (pintype "passive"))
      (node (ref "R85") (pin "2") (pinfunction "2_2") (pintype "passive"))
      (node (ref "U12") (pin "2") (pinfunction "IN1-_2") (pintype "passive"))
    )
    (net (code "59") (name "Net-(U12A-OUT1)") (class "Default")
      (node (ref "C64") (pin "2") (pinfunction "2_2") (pintype "passive"))
      (node (ref "R84") (pin "1") (pinfunction "1_1") (pintype "passive"))
      (node (ref "U12") (pin "1") (pinfunction "OUT1_1") (pintype "passive"))
    )
    (net (code "60") (name "Net-(U12B-IN2+)") (class "Default")
      (node (ref "U12") (pin "5") (pinfunction "IN2+_5") (pintype "passive"))
      (node (ref "VR1") (pin "2") (pinfunction "2_2") (pintype "passive"))
    )
    (net (code "61") (name "Net-(U12B-IN2-)") (class "Default")
      (node (ref "C51") (pin "1") (pinfunction "1_1") (pintype "passive"))
      (node (ref "R66") (pin "2") (pinfunction "2_2") (pintype "passive"))
      (node (ref "R67") (pin "2") (pinfunction "2_2") (pintype "passive"))
      (node (ref "U12") (pin "6") (pinfunction "IN2-_6") (pintype "passive"))
    )
    (net (code "62") (name "Net-(U12B-OUT2)") (class "Default")
      (node (ref "C52") (pin "1") (pinfunction "1_1") (pintype "passive"))
      (node (ref "R68") (pin "1") (pinfunction "1_1") (pintype "passive"))
      (node (ref "U12") (pin "7") (pinfunction "OUT2_7") (pintype "passive"))
    )
    (net (code "63") (name "unconnected-(RL4-Pad3A)") (class "Default")
      (node (ref "RL4") (pin "3A") (pinfunction "3A_3A") (pintype "passive"))
    )
    (net (code "64") (name "unconnected-(RL4-Pad3B)") (class "Default")
      (node (ref "RL4") (pin "3B") (pinfunction "3B_3B") (pintype "passive"))
    )
  )
)
